# compute_module_microsd.net
KiCad netlist of a schematic drawn in Altium Designer
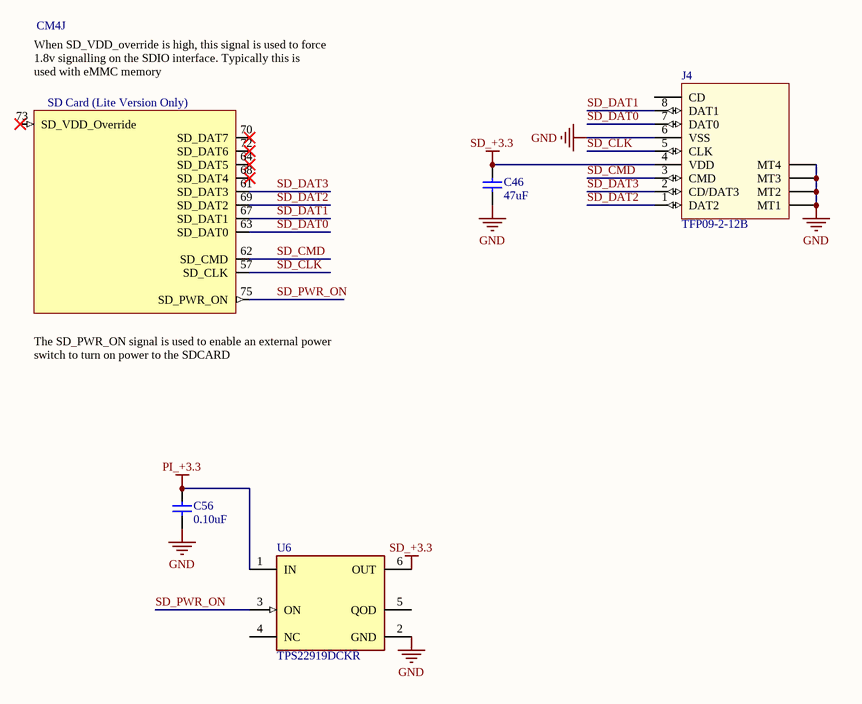
[diagram p0: compute module microsd.SchDoc]

(export (version "E")
  (design (tool "Eeschema 10.0.6"))
  (components
    (comp (ref "C46")
      (value "47uF")
      (footprint "CAPC1608X09L")
      (description "CAP CER 47UF 6.3V X5R 0603")
      (fields
        (field (name "PARTNUMBER") "ZRB18AR60J476ME01L")
        (field (name "DIGI-KEY PART NUMBER") "490-13255-1-ND")
      )
      (libsource (lib "cap_murata") (part "CAPACITOR"))
    )
    (comp (ref "C56")
      (value "0.10uF")
      (footprint "CAPC1005X06L")
      (description "CAP CER 0.1UF 10V X5R 0402")
      (fields
        (field (name "PARTNUMBER") "GRM155R61A104KA01D")
        (field (name "DIGI-KEY PART NUMBER") "490-1318-1-ND")
      )
      (libsource (lib "cap_murata") (part "CAPACITOR"))
    )
    (comp (ref "CM4")
      (value "Raspberry Pi Compute Module 4")
      (footprint "CM4-F40C-100DS-0.4v_1.5mm_0mm")
      (description "Raspberry Pi Compute Module 4 by Amornthep Phunsin")
      (libsource (lib "CM4") (part "CM4"))
    )
    (comp (ref "J4")
      (value "TFP09-2-12B")
      (footprint "TFP09-2-12B")
      (description "Micro SD Card Connector")
      (fields (field (name "MANUFACTURER") "Unknown/Generic"))
      (libsource (lib "Blinkinlabs") (part "TFP09-2-12B"))
    )
    (comp (ref "U6")
      (value "TPS22919DCKR")
      (footprint "FP-DCK0006A-MFG")
      (description "POWER MANAGEMENT")
      (libsource (lib "Altium Content Vault") (part "7dede5ae6ec4f64f362f8612ed9bb45"))
    )
  )
  (nets
    (net (code "1") (name "/SD_CLK") (class "Default")
      (node (ref "CM4") (pin "57") (pinfunction "SD_CLK_57") (pintype "passive"))
      (node (ref "J4") (pin "5") (pinfunction "CLK_5") (pintype "bidirectional"))
    )
    (net (code "2") (name "/SD_CMD") (class "Default")
      (node (ref "CM4") (pin "62") (pinfunction "SD_CMD_62") (pintype "passive"))
      (node (ref "J4") (pin "3") (pinfunction "CMD_3") (pintype "bidirectional"))
    )
    (net (code "3") (name "/SD_DAT0") (class "Default")
      (node (ref "CM4") (pin "63") (pinfunction "SD_DAT0_63") (pintype "passive"))
      (node (ref "J4") (pin "7") (pinfunction "DAT0_7") (pintype "bidirectional"))
    )
    (net (code "4") (name "/SD_DAT1") (class "Default")
      (node (ref "CM4") (pin "67") (pinfunction "SD_DAT1_67") (pintype "passive"))
      (node (ref "J4") (pin "8") (pinfunction "DAT1_8") (pintype "bidirectional"))
    )
    (net (code "5") (name "/SD_DAT2") (class "Default")
      (node (ref "CM4") (pin "69") (pinfunction "SD_DAT2_69") (pintype "passive"))
      (node (ref "J4") (pin "1") (pinfunction "DAT2_1") (pintype "bidirectional"))
    )
    (net (code "6") (name "/SD_DAT3") (class "Default")
      (node (ref "CM4") (pin "61") (pinfunction "SD_DAT3_61") (pintype "passive"))
      (node (ref "J4") (pin "2") (pinfunction "CD/DAT3_2") (pintype "bidirectional"))
    )
    (net (code "7") (name "/SD_PWR_ON") (class "Default")
      (node (ref "CM4") (pin "75") (pinfunction "SD_PWR_ON_75") (pintype "output"))
      (node (ref "U6") (pin "3") (pinfunction "ON_3") (pintype "input"))
    )
    (net (code "8") (name "GND") (class "Default")
      (node (ref "C46") (pin "2") (pinfunction "2_2") (pintype "passive"))
      (node (ref "C56") (pin "1") (pinfunction "1_1") (pintype "passive"))
      (node (ref "J4") (pin "6") (pinfunction "VSS_6") (pintype "power_in"))
      (node (ref "J4") (pin "MT1") (pinfunction "MT1_MT1") (pintype "passive"))
      (node (ref "J4") (pin "MT2") (pinfunction "MT2_MT2") (pintype "passive"))
      (node (ref "J4") (pin "MT3") (pinfunction "MT3_MT3") (pintype "passive"))
      (node (ref "J4") (pin "MT4") (pinfunction "MT4_MT4") (pintype "passive"))
      (node (ref "U6") (pin "2") (pinfunction "GND_2") (pintype "power_in"))
    )
    (net (code "9") (name "PI_+3.3") (class "Default")
      (node (ref "C56") (pin "2") (pinfunction "2_2") (pintype "passive"))
      (node (ref "U6") (pin "1") (pinfunction "IN_1") (pintype "power_in"))
    )
    (net (code "10") (name "SD_+3.3") (class "Default")
      (node (ref "C46") (pin "1") (pinfunction "1_1") (pintype "passive"))
      (node (ref "J4") (pin "4") (pinfunction "VDD_4") (pintype "power_in"))
      (node (ref "U6") (pin "6") (pinfunction "OUT_6") (pintype "power_in"))
    )
    (net (code "11") (name "unconnected-(CM4J-SD_DAT4-Pad68)") (class "Default")
      (node (ref "CM4") (pin "68") (pinfunction "SD_DAT4_68") (pintype "passive+no_connect"))
    )
    (net (code "12") (name "unconnected-(CM4J-SD_DAT5-Pad64)") (class "Default")
      (node (ref "CM4") (pin "64") (pinfunction "SD_DAT5_64") (pintype "passive+no_connect"))
    )
    (net (code "13") (name "unconnected-(CM4J-SD_DAT6-Pad72)") (class "Default")
      (node (ref "CM4") (pin "72") (pinfunction "SD_DAT6_72") (pintype "passive+no_connect"))
    )
    (net (code "14") (name "unconnected-(CM4J-SD_DAT7-Pad70)") (class "Default")
      (node (ref "CM4") (pin "70") (pinfunction "SD_DAT7_70") (pintype "passive+no_connect"))
    )
    (net (code "15") (name "unconnected-(CM4J-SD_VDD_Override-Pad73)") (class "Default")
      (node (ref "CM4") (pin "73") (pinfunction "SD_VDD_Override_73") (pintype "input+no_connect"))
    )
    (net (code "16") (name "unconnected-(J4-PadCD)") (class "Default")
      (node (ref "J4") (pin "CD") (pinfunction "CD_CD") (pintype "passive"))
    )
    (net (code "17") (name "unconnected-(U6-NC-Pad4)") (class "Default")
      (node (ref "U6") (pin "4") (pinfunction "NC_4") (pintype "passive"))
    )
    (net (code "18") (name "unconnected-(U6-QOD-Pad5)") (class "Default")
      (node (ref "U6") (pin "5") (pinfunction "QOD_5") (pintype "passive"))
    )
  )
)
